# module_JDY08.net
KiCad netlist of a schematic drawn in EAGLE
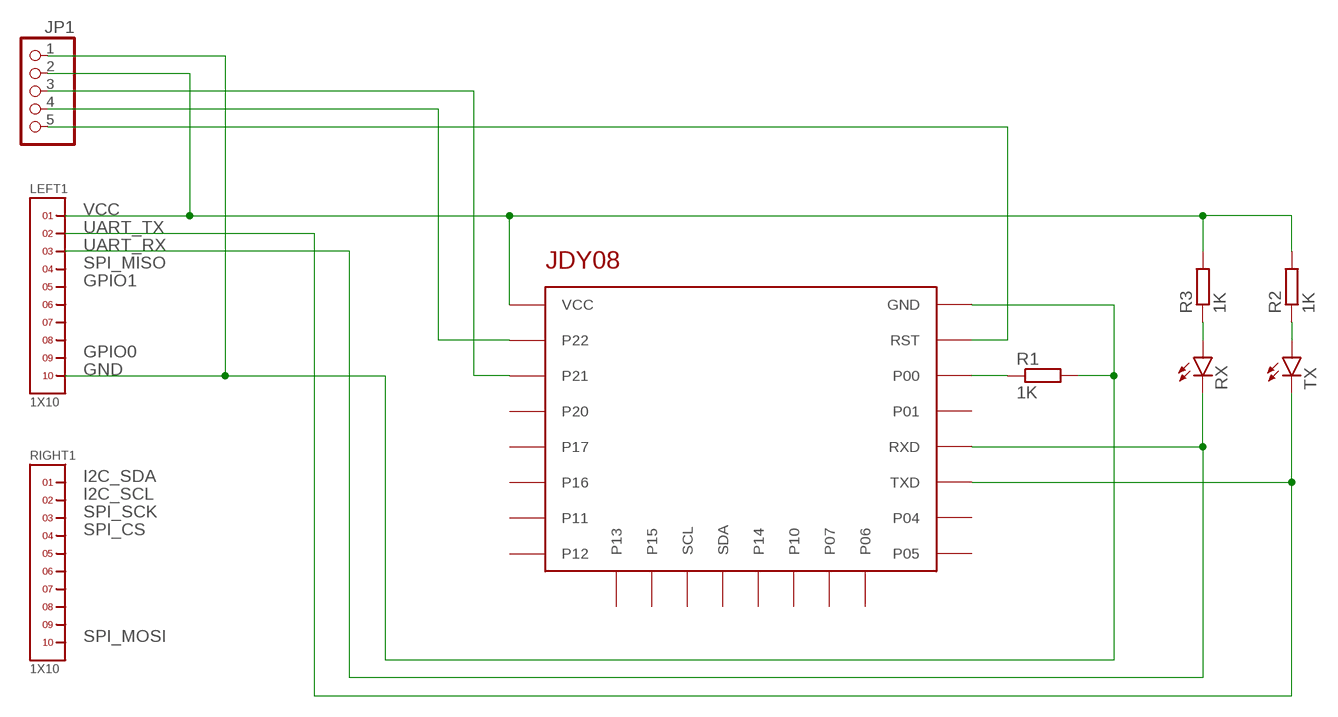
[diagram p0: schematic, sheet 1]

(export (version "E")
  (design (tool "Eeschema 10.0.6"))
  (components
    (comp (ref "JP1")
      (value "PINHD-1X5")
      (footprint "eagle-import:1X05")
      (libsource (lib "eagle-import") (part "PINHD-1X5"))
    )
    (comp (ref "LEFT1")
      (value "1X10")
      (footprint "eagle-import:1X10")
      (libsource (lib "eagle-import") (part "1X10"))
    )
    (comp (ref "R1")
      (value "1K")
      (footprint "eagle-import:R0603")
      (libsource (lib "eagle-import") (part "R-EU_R0603"))
    )
    (comp (ref "R2")
      (value "1K")
      (footprint "eagle-import:R0603")
      (libsource (lib "eagle-import") (part "R-EU_R0603"))
    )
    (comp (ref "R3")
      (value "1K")
      (footprint "eagle-import:R0603")
      (libsource (lib "eagle-import") (part "R-EU_R0603"))
    )
    (comp (ref "RIGHT1")
      (value "1X10")
      (footprint "eagle-import:1X10")
      (libsource (lib "eagle-import") (part "1X10"))
    )
    (comp (ref "RX")
      (value "LEDCHIPLED_0603")
      (footprint "eagle-import:CHIPLED_0603")
      (libsource (lib "eagle-import") (part "LEDCHIPLED_0603"))
    )
    (comp (ref "TX")
      (value "LEDCHIPLED_0603")
      (footprint "eagle-import:CHIPLED_0603")
      (libsource (lib "eagle-import") (part "LEDCHIPLED_0603"))
    )
    (comp (ref "U$1")
      (value "JDY08")
      (footprint "eagle-import:JDY08")
      (libsource (lib "eagle-import") (part "JDY08"))
    )
  )
  (nets
    (net (code "1") (name "Net-(JP1-Pad1)") (class "Default")
      (node (ref "JP1") (pin "1") (pinfunction "1_1") (pintype "passive"))
      (node (ref "LEFT1") (pin "10") (pinfunction "10_10") (pintype "bidirectional"))
      (node (ref "R1") (pin "2") (pinfunction "2_2") (pintype "passive"))
      (node (ref "U$1") (pin "GND") (pinfunction "GND_GND") (pintype "bidirectional"))
    )
    (net (code "2") (name "Net-(JP1-Pad2)") (class "Default")
      (node (ref "JP1") (pin "2") (pinfunction "2_2") (pintype "passive"))
      (node (ref "LEFT1") (pin "1") (pinfunction "1_1") (pintype "bidirectional"))
      (node (ref "R2") (pin "2") (pinfunction "2_2") (pintype "passive"))
      (node (ref "R3") (pin "2") (pinfunction "2_2") (pintype "passive"))
      (node (ref "U$1") (pin "VCC") (pinfunction "VCC_VCC") (pintype "bidirectional"))
    )
    (net (code "3") (name "Net-(JP1-Pad3)") (class "Default")
      (node (ref "JP1") (pin "3") (pinfunction "3_3") (pintype "passive"))
      (node (ref "U$1") (pin "P21") (pinfunction "P21_P21") (pintype "bidirectional"))
    )
    (net (code "4") (name "Net-(JP1-Pad4)") (class "Default")
      (node (ref "JP1") (pin "4") (pinfunction "4_4") (pintype "passive"))
      (node (ref "U$1") (pin "P22") (pinfunction "P22_P22") (pintype "bidirectional"))
    )
    (net (code "5") (name "Net-(JP1-Pad5)") (class "Default")
      (node (ref "JP1") (pin "5") (pinfunction "5_5") (pintype "passive"))
      (node (ref "U$1") (pin "RST") (pinfunction "RST_RST") (pintype "bidirectional"))
    )
    (net (code "6") (name "Net-(LEFT1-Pad2)") (class "Default")
      (node (ref "LEFT1") (pin "2") (pinfunction "2_2") (pintype "bidirectional"))
      (node (ref "TX") (pin "C") (pinfunction "C_C") (pintype "passive"))
      (node (ref "U$1") (pin "TXD") (pinfunction "TXD_TXD") (pintype "bidirectional"))
    )
    (net (code "7") (name "Net-(LEFT1-Pad3)") (class "Default")
      (node (ref "LEFT1") (pin "3") (pinfunction "3_3") (pintype "bidirectional"))
      (node (ref "RX") (pin "C") (pinfunction "C_C") (pintype "passive"))
      (node (ref "U$1") (pin "RXD") (pinfunction "RXD_RXD") (pintype "bidirectional"))
    )
    (net (code "8") (name "Net-(R1-Pad1)") (class "Default")
      (node (ref "R1") (pin "1") (pinfunction "1_1") (pintype "passive"))
      (node (ref "U$1") (pin "P00") (pinfunction "P00_P00") (pintype "bidirectional"))
    )
    (net (code "9") (name "Net-(R2-Pad1)") (class "Default")
      (node (ref "R2") (pin "1") (pinfunction "1_1") (pintype "passive"))
      (node (ref "TX") (pin "A") (pinfunction "A_A") (pintype "passive"))
    )
    (net (code "10") (name "Net-(R3-Pad1)") (class "Default")
      (node (ref "R3") (pin "1") (pinfunction "1_1") (pintype "passive"))
      (node (ref "RX") (pin "A") (pinfunction "A_A") (pintype "passive"))
    )
    (net (code "11") (name "unconnected-(LEFT1-Pad4)") (class "Default")
      (node (ref "LEFT1") (pin "4") (pinfunction "4_4") (pintype "bidirectional"))
    )
    (net (code "12") (name "unconnected-(LEFT1-Pad5)") (class "Default")
      (node (ref "LEFT1") (pin "5") (pinfunction "5_5") (pintype "bidirectional"))
    )
    (net (code "13") (name "unconnected-(LEFT1-Pad6)") (class "Default")
      (node (ref "LEFT1") (pin "6") (pinfunction "6_6") (pintype "bidirectional"))
    )
    (net (code "14") (name "unconnected-(LEFT1-Pad7)") (class "Default")
      (node (ref "LEFT1") (pin "7") (pinfunction "7_7") (pintype "bidirectional"))
    )
    (net (code "15") (name "unconnected-(LEFT1-Pad8)") (class "Default")
      (node (ref "LEFT1") (pin "8") (pinfunction "8_8") (pintype "bidirectional"))
    )
    (net (code "16") (name "unconnected-(LEFT1-Pad9)") (class "Default")
      (node (ref "LEFT1") (pin "9") (pinfunction "9_9") (pintype "bidirectional"))
    )
    (net (code "17") (name "unconnected-(RIGHT1-Pad1)") (class "Default")
      (node (ref "RIGHT1") (pin "1") (pinfunction "1_1") (pintype "bidirectional"))
    )
    (net (code "18") (name "unconnected-(RIGHT1-Pad2)") (class "Default")
      (node (ref "RIGHT1") (pin "2") (pinfunction "2_2") (pintype "bidirectional"))
    )
    (net (code "19") (name "unconnected-(RIGHT1-Pad3)") (class "Default")
      (node (ref "RIGHT1") (pin "3") (pinfunction "3_3") (pintype "bidirectional"))
    )
    (net (code "20") (name "unconnected-(RIGHT1-Pad4)") (class "Default")
      (node (ref "RIGHT1") (pin "4") (pinfunction "4_4") (pintype "bidirectional"))
    )
    (net (code "21") (name "unconnected-(RIGHT1-Pad5)") (class "Default")
      (node (ref "RIGHT1") (pin "5") (pinfunction "5_5") (pintype "bidirectional"))
    )
    (net (code "22") (name "unconnected-(RIGHT1-Pad6)") (class "Default")
      (node (ref "RIGHT1") (pin "6") (pinfunction "6_6") (pintype "bidirectional"))
    )
    (net (code "23") (name "unconnected-(RIGHT1-Pad7)") (class "Default")
      (node (ref "RIGHT1") (pin "7") (pinfunction "7_7") (pintype "bidirectional"))
    )
    (net (code "24") (name "unconnected-(RIGHT1-Pad8)") (class "Default")
      (node (ref "RIGHT1") (pin "8") (pinfunction "8_8") (pintype "bidirectional"))
    )
    (net (code "25") (name "unconnected-(RIGHT1-Pad9)") (class "Default")
      (node (ref "RIGHT1") (pin "9") (pinfunction "9_9") (pintype "bidirectional"))
    )
    (net (code "26") (name "unconnected-(RIGHT1-Pad10)") (class "Default")
      (node (ref "RIGHT1") (pin "10") (pinfunction "10_10") (pintype "bidirectional"))
    )
    (net (code "27") (name "unconnected-(U$1-PadP01)") (class "Default")
      (node (ref "U$1") (pin "P01") (pinfunction "P01_P01") (pintype "bidirectional"))
    )
    (net (code "28") (name "unconnected-(U$1-PadP04)") (class "Default")
      (node (ref "U$1") (pin "P04") (pinfunction "P04_P04") (pintype "bidirectional"))
    )
    (net (code "29") (name "unconnected-(U$1-PadP05)") (class "Default")
      (node (ref "U$1") (pin "P05") (pinfunction "P05_P05") (pintype "bidirectional"))
    )
    (net (code "30") (name "unconnected-(U$1-PadP06)") (class "Default")
      (node (ref "U$1") (pin "P06") (pinfunction "P06_P06") (pintype "bidirectional"))
    )
    (net (code "31") (name "unconnected-(U$1-PadP07)") (class "Default")
      (node (ref "U$1") (pin "P07") (pinfunction "P07_P07") (pintype "bidirectional"))
    )
    (net (code "32") (name "unconnected-(U$1-PadP10)") (class "Default")
      (node (ref "U$1") (pin "P10") (pinfunction "P10_P10") (pintype "bidirectional"))
    )
    (net (code "33") (name "unconnected-(U$1-PadP11)") (class "Default")
      (node (ref "U$1") (pin "P11") (pinfunction "P11_P11") (pintype "bidirectional"))
    )
    (net (code "34") (name "unconnected-(U$1-PadP12)") (class "Default")
      (node (ref "U$1") (pin "P12") (pinfunction "P12_P12") (pintype "bidirectional"))
    )
    (net (code "35") (name "unconnected-(U$1-PadP13)") (class "Default")
      (node (ref "U$1") (pin "P13") (pinfunction "P13_P13") (pintype "bidirectional"))
    )
    (net (code "36") (name "unconnected-(U$1-PadP14)") (class "Default")
      (node (ref "U$1") (pin "P14") (pinfunction "P14_P14") (pintype "bidirectional"))
    )
    (net (code "37") (name "unconnected-(U$1-PadP15)") (class "Default")
      (node (ref "U$1") (pin "P15") (pinfunction "P15_P15") (pintype "bidirectional"))
    )
    (net (code "38") (name "unconnected-(U$1-PadP16)") (class "Default")
      (node (ref "U$1") (pin "P16") (pinfunction "P16_P16") (pintype "bidirectional"))
    )
    (net (code "39") (name "unconnected-(U$1-PadP17)") (class "Default")
      (node (ref "U$1") (pin "P17") (pinfunction "P17_P17") (pintype "bidirectional"))
    )
    (net (code "40") (name "unconnected-(U$1-PadP20)") (class "Default")
      (node (ref "U$1") (pin "P20") (pinfunction "P20_P20") (pintype "bidirectional"))
    )
    (net (code "41") (name "unconnected-(U$1-PadSCL)") (class "Default")
      (node (ref "U$1") (pin "SCL") (pinfunction "SCL_SCL") (pintype "bidirectional"))
    )
    (net (code "42") (name "unconnected-(U$1-PadSDA)") (class "Default")
      (node (ref "U$1") (pin "SDA") (pinfunction "SDA_SDA") (pintype "bidirectional"))
    )
  )
)
